# BatteruPSU_SM-reg.net
KiCad netlist of a schematic drawn in Altium Designer
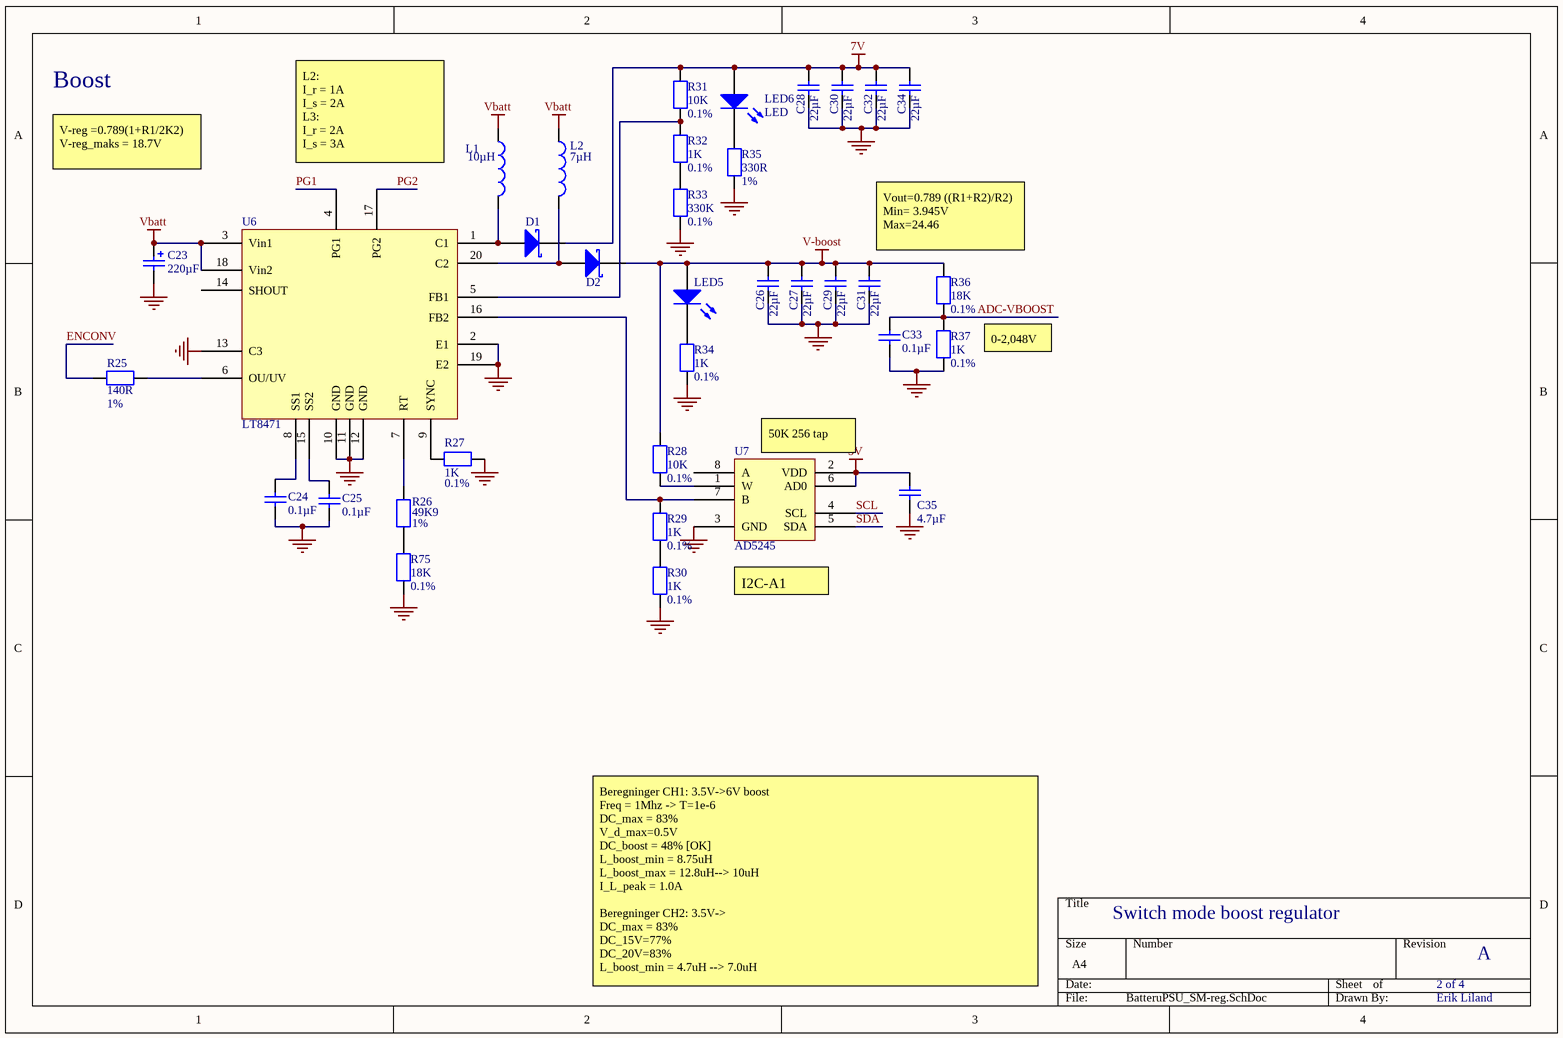
[diagram p0: BatteruPSU_SM-reg.SchDoc]

(export (version "E")
  (design (tool "Eeschema 10.0.6"))
  (components
    (comp (ref "C23")
      (value "220µF")
      (footprint "BatteruPSU:CAP SMD (F)")
      (description "Polarized Capacitor")
      (fields
        (field (name "MANUFACTURER") "Panasonic Electronic Components")
        (field (name "MANUFACTURER PART NUMBER") "EEH-ZA1E221P")
      )
      (libsource (lib "BatteryPSU-parts") (part "Cap Pol"))
    )
    (comp (ref "C24")
      (value "0.1µF")
      (footprint "BatteruPSU:0805_N_CAP")
      (description "Capacitor")
      (fields
        (field (name "MANUFACTURER") "Kemet")
        (field (name "MANUFACTURER PART NUMBER") "C0805C104K4RACTU")
      )
      (libsource (lib "BatteryPSU-parts") (part "Cap"))
    )
    (comp (ref "C25")
      (value "0.1µF")
      (footprint "BatteruPSU:0805_N_CAP")
      (description "Capacitor")
      (fields
        (field (name "MANUFACTURER") "Kemet")
        (field (name "MANUFACTURER PART NUMBER") "C0805C104K4RACTU")
      )
      (libsource (lib "BatteryPSU-parts") (part "Cap"))
    )
    (comp (ref "C26")
      (value "22µF")
      (footprint "BatteruPSU:0805_N_CAP")
      (description "Capacitor")
      (fields
        (field (name "MANUFACTURER") "TDK Corporation")
        (field (name "MANUFACTURER PART NUMBER") "C2012X5R1V226M125AC")
      )
      (libsource (lib "BatteryPSU-parts") (part "Cap"))
    )
    (comp (ref "C27")
      (value "22µF")
      (footprint "BatteruPSU:0805_N_CAP")
      (description "Capacitor")
      (fields
        (field (name "MANUFACTURER") "TDK Corporation")
        (field (name "MANUFACTURER PART NUMBER") "C2012X5R1V226M125AC")
      )
      (libsource (lib "BatteryPSU-parts") (part "Cap"))
    )
    (comp (ref "C28")
      (value "22µF")
      (footprint "BatteruPSU:0805_N_CAP")
      (description "Capacitor")
      (fields
        (field (name "MANUFACTURER") "Murata Electronics North America")
        (field (name "MANUFACTURER PART NUMBER") "GRM21BR61A226ME51L")
      )
      (libsource (lib "BatteryPSU-parts") (part "Cap"))
    )
    (comp (ref "C29")
      (value "22µF")
      (footprint "BatteruPSU:0805_N_CAP")
      (description "Capacitor")
      (fields
        (field (name "MANUFACTURER") "TDK Corporation")
        (field (name "MANUFACTURER PART NUMBER") "C2012X5R1V226M125AC")
      )
      (libsource (lib "BatteryPSU-parts") (part "Cap"))
    )
    (comp (ref "C30")
      (value "22µF")
      (footprint "BatteruPSU:0805_N_CAP")
      (description "Capacitor")
      (fields
        (field (name "MANUFACTURER") "Murata Electronics North America")
        (field (name "MANUFACTURER PART NUMBER") "GRM21BR61A226ME51L")
      )
      (libsource (lib "BatteryPSU-parts") (part "Cap"))
    )
    (comp (ref "C31")
      (value "22µF")
      (footprint "BatteruPSU:0805_N_CAP")
      (description "Capacitor")
      (fields
        (field (name "MANUFACTURER") "TDK Corporation")
        (field (name "MANUFACTURER PART NUMBER") "C2012X5R1V226M125AC")
      )
      (libsource (lib "BatteryPSU-parts") (part "Cap"))
    )
    (comp (ref "C32")
      (value "22µF")
      (footprint "BatteruPSU:0805_N_CAP")
      (description "Capacitor")
      (fields
        (field (name "MANUFACTURER") "Murata Electronics North America")
        (field (name "MANUFACTURER PART NUMBER") "GRM21BR61A226ME51L")
      )
      (libsource (lib "BatteryPSU-parts") (part "Cap"))
    )
    (comp (ref "C33")
      (value "0.1µF")
      (footprint "BatteruPSU:0805_N_CAP")
      (description "Capacitor")
      (fields
        (field (name "MANUFACTURER") "Kemet")
        (field (name "MANUFACTURER PART NUMBER") "C0805C104K4RACTU")
      )
      (libsource (lib "BatteryPSU-parts") (part "Cap"))
    )
    (comp (ref "C34")
      (value "22µF")
      (footprint "BatteruPSU:0805_N_CAP")
      (description "Capacitor")
      (fields
        (field (name "MANUFACTURER") "Murata Electronics North America")
        (field (name "MANUFACTURER PART NUMBER") "GRM21BR61A226ME51L")
      )
      (libsource (lib "BatteryPSU-parts") (part "Cap"))
    )
    (comp (ref "C35")
      (value "4.7µF")
      (footprint "BatteruPSU:0805_N_CAP")
      (description "Capacitor")
      (fields
        (field (name "MANUFACTURER") "Samsung Electro-Mechanics America, Inc")
        (field (name "MANUFACTURER PART NUMBER") "CL21B475KOFNFNE")
      )
      (libsource (lib "BatteryPSU-parts") (part "Cap"))
    )
    (comp (ref "D1")
      (value "D Schottky")
      (footprint "DO-214AC, SMA")
      (description "Schottky Diode")
      (fields
        (field (name "MANUFACTURER") "Micro Commercial Co")
        (field (name "MANUFACTURER PART NUMBER") "SK33A-TP")
        (field (name "PUBLISHER") "Altium Limited")
      )
      (libsource (lib "BatteryPSU-parts") (part "D Schottky"))
    )
    (comp (ref "D2")
      (value "D Schottky")
      (footprint "DO-214AC, SMA")
      (description "Schottky Diode")
      (fields
        (field (name "MANUFACTURER") "Micro Commercial Co")
        (field (name "MANUFACTURER PART NUMBER") "SK33A-TP")
        (field (name "PUBLISHER") "Altium Limited")
      )
      (libsource (lib "BatteryPSU-parts") (part "D Schottky"))
    )
    (comp (ref "L1")
      (value "Inductor")
      (footprint "BatteruPSU:Inductor wirewound")
      (fields
        (field (name "MANUFACTURER") "Bourns Inc.")
        (field (name "MANUFACTURER PART NUMBER") "SRR1005-100M")
        (field (name "INDUCTANCE") "10µH")
        (field (name "TOLERANCE") "±20%")
      )
      (libsource (lib "BatteryPSU-parts") (part "Inductor"))
    )
    (comp (ref "L2")
      (value "Inductor")
      (footprint "BatteruPSU:Inductor wirewound")
      (fields
        (field (name "MANUFACTURER") "Bourns Inc.")
        (field (name "MANUFACTURER PART NUMBER") "SRR1005-7R0M")
        (field (name "INDUCTANCE") "7µH")
        (field (name "TOLERANCE") "±20%")
      )
      (libsource (lib "BatteryPSU-parts") (part "Inductor"))
    )
    (comp (ref "LED5")
      (value "LED")
      (footprint "BatteruPSU:0805_N_LED")
      (description "Typical RED, GREEN, YELLOW, AMBER")
      (fields
        (field (name "MANUFACTURER") "OSRAM Opto Semiconductors Inc")
        (field (name "MANUFACTURER PART NUMBER") "LG R971-KN-1")
      )
      (libsource (lib "BatteryPSU-parts") (part "LED"))
    )
    (comp (ref "LED6")
      (value "LED")
      (footprint "BatteruPSU:0805_N_LED")
      (description "Typical RED, GREEN, YELLOW, AMBER")
      (fields
        (field (name "MANUFACTURER") "OSRAM Opto Semiconductors Inc")
        (field (name "MANUFACTURER PART NUMBER") "LG R971-KN-1")
      )
      (libsource (lib "BatteryPSU-parts") (part "LED"))
    )
    (comp (ref "R25")
      (value "140R")
      (footprint "BatteruPSU:0805_N_RES")
      (description "Resistor")
      (fields
        (field (name "TOLERANCE") "1%")
        (field (name "MANUFACTURER") "Samsung Electro-Mechanics America, Inc")
        (field (name "MANUFACTURER PART NUMBER") "RC2012F1400CS")
      )
      (libsource (lib "BatteryPSU-parts") (part "Res"))
    )
    (comp (ref "R26")
      (value "49K9")
      (footprint "BatteruPSU:0805_N_RES")
      (description "Resistor")
      (fields
        (field (name "TOLERANCE") "1%")
        (field (name "MANUFACTURER") "Samsung Electro-Mechanics America, Inc")
        (field (name "MANUFACTURER PART NUMBER") "RC2012F4992CS")
      )
      (libsource (lib "") (part "Res_1"))
    )
    (comp (ref "R27")
      (value "1K")
      (footprint "BatteruPSU:0805_N_RES")
      (description "Resistor")
      (fields
        (field (name "TOLERANCE") "0.1%")
        (field (name "MANUFACTURER") "Panasonic Electronic Components")
        (field (name "MANUFACTURER PART NUMBER") "ERA-6AEB102V")
      )
      (libsource (lib "BatteryPSU-parts") (part "Res"))
    )
    (comp (ref "R28")
      (value "10K")
      (footprint "BatteruPSU:0805_N_RES")
      (description "Resistor")
      (fields
        (field (name "TOLERANCE") "0.1%")
        (field (name "MANUFACTURER") "TE Connectivity AMP Connectors")
        (field (name "MANUFACTURER PART NUMBER") "8-1614884-4")
      )
      (libsource (lib "") (part "Res_1"))
    )
    (comp (ref "R29")
      (value "1K")
      (footprint "BatteruPSU:0805_N_RES")
      (description "Resistor")
      (fields
        (field (name "TOLERANCE") "0.1%")
        (field (name "MANUFACTURER") "Panasonic Electronic Components")
        (field (name "MANUFACTURER PART NUMBER") "ERA-6AEB102V")
      )
      (libsource (lib "") (part "Res_1"))
    )
    (comp (ref "R30")
      (value "1K")
      (footprint "BatteruPSU:0805_N_RES")
      (description "Resistor")
      (fields
        (field (name "TOLERANCE") "0.1%")
        (field (name "MANUFACTURER") "Panasonic Electronic Components")
        (field (name "MANUFACTURER PART NUMBER") "ERA-6AEB102V")
      )
      (libsource (lib "") (part "Res_1"))
    )
    (comp (ref "R31")
      (value "10K")
      (footprint "BatteruPSU:0805_N_RES")
      (description "Resistor")
      (fields
        (field (name "TOLERANCE") "0.1%")
        (field (name "MANUFACTURER") "TE Connectivity AMP Connectors")
        (field (name "MANUFACTURER PART NUMBER") "8-1614884-4")
      )
      (libsource (lib "") (part "Res_1"))
    )
    (comp (ref "R32")
      (value "1K")
      (footprint "BatteruPSU:0805_N_RES")
      (description "Resistor")
      (fields
        (field (name "TOLERANCE") "0.1%")
        (field (name "MANUFACTURER") "Panasonic Electronic Components")
        (field (name "MANUFACTURER PART NUMBER") "ERA-6AEB102V")
      )
      (libsource (lib "") (part "Res_1"))
    )
    (comp (ref "R33")
      (value "330K")
      (footprint "BatteruPSU:0805_N_RES")
      (description "Resistor")
      (fields
        (field (name "TOLERANCE") "0.1%")
        (field (name "MANUFACTURER") "TE Connectivity AMP Connectors")
        (field (name "MANUFACTURER PART NUMBER") "8-1614884-4")
      )
      (libsource (lib "") (part "Res_2"))
    )
    (comp (ref "R34")
      (value "1K")
      (footprint "BatteruPSU:0805_N_RES")
      (description "Resistor")
      (fields
        (field (name "TOLERANCE") "0.1%")
        (field (name "MANUFACTURER") "Panasonic Electronic Components")
        (field (name "MANUFACTURER PART NUMBER") "ERA-6AEB102V")
      )
      (libsource (lib "") (part "Res_1"))
    )
    (comp (ref "R35")
      (value "330R")
      (footprint "BatteruPSU:0805_N_RES")
      (description "Resistor")
      (fields
        (field (name "TOLERANCE") "1%")
        (field (name "MANUFACTURER") "Samsung Electro-Mechanics America, Inc")
        (field (name "MANUFACTURER PART NUMBER") "RC2012F1400CS")
      )
      (libsource (lib "") (part "Res_2"))
    )
    (comp (ref "R36")
      (value "18K")
      (footprint "BatteruPSU:0805_N_RES")
      (description "Resistor")
      (fields
        (field (name "TOLERANCE") "0.1%")
        (field (name "MANUFACTURER") "Panasonic Electronic Components")
        (field (name "MANUFACTURER PART NUMBER") "ERA-6AEB183V")
      )
      (libsource (lib "") (part "Res_2"))
    )
    (comp (ref "R37")
      (value "1K")
      (footprint "BatteruPSU:0805_N_RES")
      (description "Resistor")
      (fields
        (field (name "TOLERANCE") "0.1%")
        (field (name "MANUFACTURER") "Panasonic Electronic Components")
        (field (name "MANUFACTURER PART NUMBER") "ERA-6AEB102V")
      )
      (libsource (lib "") (part "Res_2"))
    )
    (comp (ref "R75")
      (value "18K")
      (footprint "BatteruPSU:0805_N_RES")
      (description "Resistor")
      (fields
        (field (name "TOLERANCE") "0.1%")
        (field (name "MANUFACTURER") "Panasonic Electronic Components")
        (field (name "MANUFACTURER PART NUMBER") "ERA-6AEB183V")
      )
      (libsource (lib "") (part "Res_2"))
    )
    (comp (ref "U6")
      (value "LT8471")
      (footprint "BatteruPSU:TSSOP20_N")
      (description "DC/DC conv")
      (fields
        (field (name "MANUFACTURER") "Linear Technology")
        (field (name "MANUFACTURER PART NUMBER") "LT8471IFE#PBF")
      )
      (libsource (lib "BatteryPSU-parts") (part "LT8471"))
    )
    (comp (ref "U7")
      (value "AD5245")
      (footprint "BatteruPSU:SOT-23-8")
      (description "DigPot")
      (fields
        (field (name "MANUFACTURER") "Analog Devices Inc")
        (field (name "MANUFACTURER PART NUMBER") "AD5245BRJZ50-RL7")
      )
      (libsource (lib "BatteryPSU-parts") (part "AD5245"))
    )
  )
  (nets
    (net (code "1") (name "/ADC-VBOOST") (class "Default")
      (node (ref "C33") (pin "2") (pinfunction "2_2") (pintype "passive"))
      (node (ref "R36") (pin "2") (pinfunction "2_2") (pintype "passive"))
      (node (ref "R37") (pin "1") (pinfunction "1_1") (pintype "passive"))
    )
    (net (code "2") (name "/ENCONV") (class "Default")
      (node (ref "R25") (pin "1") (pinfunction "1_1") (pintype "passive"))
    )
    (net (code "3") (name "/PG1") (class "Default")
      (node (ref "U6") (pin "4") (pinfunction "PG1_4") (pintype "passive"))
    )
    (net (code "4") (name "/PG2") (class "Default")
      (node (ref "U6") (pin "17") (pinfunction "PG2_17") (pintype "passive"))
    )
    (net (code "5") (name "/SCL") (class "Default")
      (node (ref "U7") (pin "4") (pinfunction "SCL_4") (pintype "passive"))
    )
    (net (code "6") (name "/SDA") (class "Default")
      (node (ref "U7") (pin "5") (pinfunction "SDA_5") (pintype "passive"))
    )
    (net (code "7") (name "5V") (class "Default")
      (node (ref "C35") (pin "1") (pinfunction "1_1") (pintype "passive"))
      (node (ref "U7") (pin "2") (pinfunction "VDD_2") (pintype "passive"))
      (node (ref "U7") (pin "6") (pinfunction "AD0_6") (pintype "passive"))
    )
    (net (code "8") (name "7V") (class "Default")
      (node (ref "C28") (pin "1") (pinfunction "1_1") (pintype "passive"))
      (node (ref "C30") (pin "1") (pinfunction "1_1") (pintype "passive"))
      (node (ref "C32") (pin "1") (pinfunction "1_1") (pintype "passive"))
      (node (ref "C34") (pin "1") (pinfunction "1_1") (pintype "passive"))
      (node (ref "D1") (pin "2") (pinfunction "K_2") (pintype "passive"))
      (node (ref "LED6") (pin "1") (pinfunction "A_1") (pintype "passive"))
      (node (ref "R31") (pin "2") (pinfunction "2_2") (pintype "passive"))
    )
    (net (code "9") (name "GND") (class "Default")
      (node (ref "C23") (pin "2") (pinfunction "2_2") (pintype "passive"))
      (node (ref "C24") (pin "1") (pinfunction "1_1") (pintype "passive"))
      (node (ref "C25") (pin "1") (pinfunction "1_1") (pintype "passive"))
      (node (ref "C26") (pin "2") (pinfunction "2_2") (pintype "passive"))
      (node (ref "C27") (pin "2") (pinfunction "2_2") (pintype "passive"))
      (node (ref "C28") (pin "2") (pinfunction "2_2") (pintype "passive"))
      (node (ref "C29") (pin "2") (pinfunction "2_2") (pintype "passive"))
      (node (ref "C30") (pin "2") (pinfunction "2_2") (pintype "passive"))
      (node (ref "C31") (pin "2") (pinfunction "2_2") (pintype "passive"))
      (node (ref "C32") (pin "2") (pinfunction "2_2") (pintype "passive"))
      (node (ref "C33") (pin "1") (pinfunction "1_1") (pintype "passive"))
      (node (ref "C34") (pin "2") (pinfunction "2_2") (pintype "passive"))
      (node (ref "C35") (pin "2") (pinfunction "2_2") (pintype "passive"))
      (node (ref "R27") (pin "2") (pinfunction "2_2") (pintype "passive"))
      (node (ref "R30") (pin "1") (pinfunction "1_1") (pintype "passive"))
      (node (ref "R33") (pin "2") (pinfunction "2_2") (pintype "passive"))
      (node (ref "R34") (pin "1") (pinfunction "1_1") (pintype "passive"))
      (node (ref "R35") (pin "2") (pinfunction "2_2") (pintype "passive"))
      (node (ref "R37") (pin "2") (pinfunction "2_2") (pintype "passive"))
      (node (ref "R75") (pin "2") (pinfunction "2_2") (pintype "passive"))
      (node (ref "U6") (pin "10") (pinfunction "GND_10") (pintype "passive"))
      (node (ref "U6") (pin "11") (pinfunction "GND_11") (pintype "passive"))
      (node (ref "U6") (pin "12") (pinfunction "GND_12") (pintype "passive"))
      (node (ref "U6") (pin "13") (pinfunction "C3_13") (pintype "passive"))
      (node (ref "U6") (pin "19") (pinfunction "E2_19") (pintype "passive"))
      (node (ref "U6") (pin "2") (pinfunction "E1_2") (pintype "passive"))
      (node (ref "U7") (pin "3") (pinfunction "GND_3") (pintype "passive"))
    )
    (net (code "10") (name "Net-(D1-A)") (class "Default")
      (node (ref "D1") (pin "1") (pinfunction "A_1") (pintype "passive"))
      (node (ref "L1") (pin "2") (pinfunction "2_2") (pintype "passive"))
      (node (ref "U6") (pin "1") (pinfunction "C1_1") (pintype "passive"))
    )
    (net (code "11") (name "Net-(D2-A)") (class "Default")
      (node (ref "D2") (pin "1") (pinfunction "A_1") (pintype "passive"))
      (node (ref "L2") (pin "2") (pinfunction "2_2") (pintype "passive"))
      (node (ref "U6") (pin "20") (pinfunction "C2_20") (pintype "passive"))
    )
    (net (code "12") (name "Net-(LED5-K)") (class "Default")
      (node (ref "LED5") (pin "2") (pinfunction "K_2") (pintype "passive"))
      (node (ref "R34") (pin "2") (pinfunction "2_2") (pintype "passive"))
    )
    (net (code "13") (name "Net-(LED6-K)") (class "Default")
      (node (ref "LED6") (pin "2") (pinfunction "K_2") (pintype "passive"))
      (node (ref "R35") (pin "1") (pinfunction "1_1") (pintype "passive"))
    )
    (net (code "14") (name "Net-(R26-Pad1)") (class "Default")
      (node (ref "R26") (pin "1") (pinfunction "1_1") (pintype "passive"))
      (node (ref "R75") (pin "1") (pinfunction "1_1") (pintype "passive"))
    )
    (net (code "15") (name "Net-(R29-Pad1)") (class "Default")
      (node (ref "R29") (pin "1") (pinfunction "1_1") (pintype "passive"))
      (node (ref "R30") (pin "2") (pinfunction "2_2") (pintype "passive"))
    )
    (net (code "16") (name "Net-(R32-Pad1)") (class "Default")
      (node (ref "R32") (pin "1") (pinfunction "1_1") (pintype "passive"))
      (node (ref "R33") (pin "1") (pinfunction "1_1") (pintype "passive"))
    )
    (net (code "17") (name "Net-(U6-FB1)") (class "Default")
      (node (ref "R31") (pin "1") (pinfunction "1_1") (pintype "passive"))
      (node (ref "R32") (pin "2") (pinfunction "2_2") (pintype "passive"))
      (node (ref "U6") (pin "5") (pinfunction "FB1_5") (pintype "passive"))
    )
    (net (code "18") (name "Net-(U6-FB2)") (class "Default")
      (node (ref "R29") (pin "2") (pinfunction "2_2") (pintype "passive"))
      (node (ref "U6") (pin "16") (pinfunction "FB2_16") (pintype "passive"))
      (node (ref "U7") (pin "7") (pinfunction "B_7") (pintype "passive"))
    )
    (net (code "19") (name "Net-(U6-OU{slash}UV)") (class "Default")
      (node (ref "R25") (pin "2") (pinfunction "2_2") (pintype "passive"))
      (node (ref "U6") (pin "6") (pinfunction "OU/UV_6") (pintype "passive"))
    )
    (net (code "20") (name "Net-(U6-RT)") (class "Default")
      (node (ref "R26") (pin "2") (pinfunction "2_2") (pintype "passive"))
      (node (ref "U6") (pin "7") (pinfunction "RT_7") (pintype "passive"))
    )
    (net (code "21") (name "Net-(U6-SS1)") (class "Default")
      (node (ref "C24") (pin "2") (pinfunction "2_2") (pintype "passive"))
      (node (ref "U6") (pin "8") (pinfunction "SS1_8") (pintype "passive"))
    )
    (net (code "22") (name "Net-(U6-SS2)") (class "Default")
      (node (ref "C25") (pin "2") (pinfunction "2_2") (pintype "passive"))
      (node (ref "U6") (pin "15") (pinfunction "SS2_15") (pintype "passive"))
    )
    (net (code "23") (name "Net-(U6-SYNC)") (class "Default")
      (node (ref "R27") (pin "1") (pinfunction "1_1") (pintype "passive"))
      (node (ref "U6") (pin "9") (pinfunction "SYNC_9") (pintype "passive"))
    )
    (net (code "24") (name "Net-(U7-W)") (class "Default")
      (node (ref "R28") (pin "1") (pinfunction "1_1") (pintype "passive"))
      (node (ref "U7") (pin "1") (pinfunction "W_1") (pintype "passive"))
    )
    (net (code "25") (name "V-boost") (class "Default")
      (node (ref "C26") (pin "1") (pinfunction "1_1") (pintype "passive"))
      (node (ref "C27") (pin "1") (pinfunction "1_1") (pintype "passive"))
      (node (ref "C29") (pin "1") (pinfunction "1_1") (pintype "passive"))
      (node (ref "C31") (pin "1") (pinfunction "1_1") (pintype "passive"))
      (node (ref "D2") (pin "2") (pinfunction "K_2") (pintype "passive"))
      (node (ref "LED5") (pin "1") (pinfunction "A_1") (pintype "passive"))
      (node (ref "R28") (pin "2") (pinfunction "2_2") (pintype "passive"))
      (node (ref "R36") (pin "1") (pinfunction "1_1") (pintype "passive"))
    )
    (net (code "26") (name "Vbatt") (class "Default")
      (node (ref "C23") (pin "1") (pinfunction "1_1") (pintype "passive"))
      (node (ref "L1") (pin "1") (pinfunction "1_1") (pintype "passive"))
      (node (ref "L2") (pin "1") (pinfunction "1_1") (pintype "passive"))
      (node (ref "U6") (pin "18") (pinfunction "Vin2_18") (pintype "passive"))
      (node (ref "U6") (pin "3") (pinfunction "Vin1_3") (pintype "passive"))
    )
    (net (code "27") (name "unconnected-(U6-SHOUT-Pad14)") (class "Default")
      (node (ref "U6") (pin "14") (pinfunction "SHOUT_14") (pintype "passive"))
    )
    (net (code "28") (name "unconnected-(U7-A-Pad8)") (class "Default")
      (node (ref "U7") (pin "8") (pinfunction "A_8") (pintype "passive"))
    )
  )
)
